# CAN_BUS.net
KiCad netlist of a schematic drawn in Altium Designer
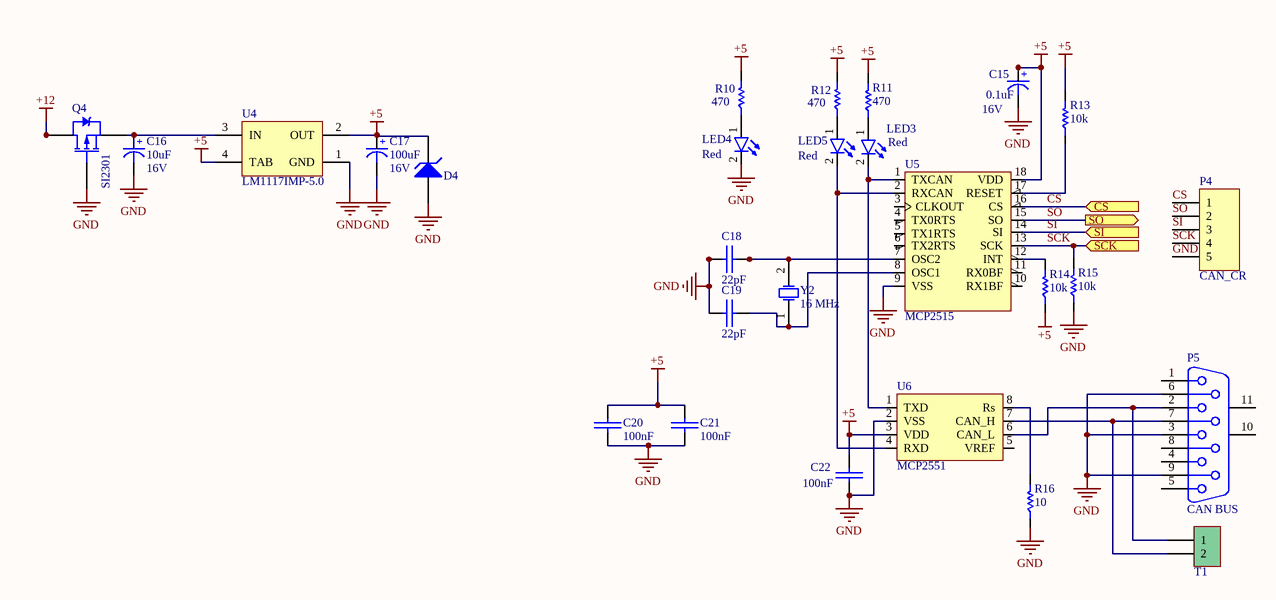
[diagram p0: CAN_BUS.SchDoc]

(export (version "E")
  (design (tool "Eeschema 10.0.6"))
  (components
    (comp (ref "C15")
      (value "0.1uF")
      (footprint "CAPP 1206 (3216X18L) Size A")
      (description "Polar Capacitor")
      (fields (field (name "VOLTAGE") "16V") (field (name "DESIGNER") "Saeid Jorablo"))
      (libsource (lib "My_Library") (part "Cap-Polar"))
    )
    (comp (ref "C16")
      (value "10uF")
      (footprint "CAPP 1206 (3216X18L) Size A")
      (description "Polar Capacitor")
      (fields (field (name "VOLTAGE") "16V") (field (name "DESIGNER") "Saeid Jorablo"))
      (libsource (lib "My_Library") (part "Cap-Polar"))
    )
    (comp (ref "C17")
      (value "100uF")
      (footprint "CAPP 1206 (3216X18L) Size A")
      (description "Polar Capacitor")
      (fields (field (name "VOLTAGE") "16V") (field (name "DESIGNER") "Saeid Jorablo"))
      (libsource (lib "My_Library") (part "Cap-Polar"))
    )
    (comp (ref "C18")
      (value "22pF")
      (footprint "SMD_CAP_1206")
      (description "Bipolar Capacitor")
      (fields (field (name "VOLTAGE") "100V") (field (name "DESIGNER") "Saeid Jorablo"))
      (libsource (lib "My_Library") (part "Cap-Bipolar"))
    )
    (comp (ref "C19")
      (value "22pF")
      (footprint "SMD_CAP_1206")
      (description "Bipolar Capacitor")
      (fields (field (name "VOLTAGE") "100V") (field (name "DESIGNER") "Saeid Jorablo"))
      (libsource (lib "My_Library") (part "Cap-Bipolar"))
    )
    (comp (ref "C20")
      (value "100nF")
      (footprint "SMD_CAP_1206")
      (description "Bipolar Capacitor")
      (fields (field (name "VOLTAGE") "100V") (field (name "DESIGNER") "Saeid Jorablo"))
      (libsource (lib "My_Library") (part "Cap-Bipolar"))
    )
    (comp (ref "C21")
      (value "100nF")
      (footprint "SMD_CAP_1206")
      (description "Bipolar Capacitor")
      (fields (field (name "VOLTAGE") "100V") (field (name "DESIGNER") "Saeid Jorablo"))
      (libsource (lib "My_Library") (part "Cap-Bipolar"))
    )
    (comp (ref "C22")
      (value "100nF")
      (footprint "SMD_CAP_1206")
      (description "Bipolar Capacitor")
      (fields (field (name "VOLTAGE") "100V") (field (name "DESIGNER") "Saeid Jorablo"))
      (libsource (lib "My_Library") (part "Cap-Bipolar"))
    )
    (comp (ref "D4")
      (value "Diode Zener")
      (footprint "Diode 1W")
      (description "Zener Diode")
      (fields (field (name "VOLTAGE") "5 V") (field (name "DESIGNER") "Saeid Jorablo"))
      (libsource (lib "My_Library") (part "Diode Zener"))
    )
    (comp (ref "LED3")
      (value "Red")
      (footprint "LED-5mm")
      (description "LED")
      (fields (field (name "COLOR") "Red") (field (name "DESIGNER") "Saeid Jorablo"))
      (libsource (lib "My_Library") (part "LED"))
    )
    (comp (ref "LED4")
      (value "Red")
      (footprint "LED-5mm")
      (description "LED")
      (fields (field (name "COLOR") "Red") (field (name "DESIGNER") "Saeid Jorablo"))
      (libsource (lib "My_Library") (part "LED"))
    )
    (comp (ref "LED5")
      (value "Red")
      (footprint "LED-5mm")
      (description "LED")
      (fields (field (name "COLOR") "Red") (field (name "DESIGNER") "Saeid Jorablo"))
      (libsource (lib "My_Library") (part "LED"))
    )
    (comp (ref "P4")
      (value "CAN_CR")
      (footprint "HDR1X5")
      (description "Header, 5-Pin")
      (fields (field (name "PUBLISHER") "Altium Limited"))
      (libsource (lib "Miscellaneous Connectors") (part "Header 5"))
    )
    (comp (ref "P5")
      (value "CAN BUS")
      (footprint "DB9 Female")
      (description "Receptacle Assembly, 9 Position, Right Angle")
      (fields (field (name "PUBLISHER") "Altium Limited"))
      (libsource (lib "My_Library") (part "DB9 Connector"))
    )
    (comp (ref "Q4")
      (value "SI2301")
      (footprint "SOT-23_M")
      (description "P-Channel Power MOSFET")
      (fields (field (name "PUBLISHER") "Altium Limited"))
      (libsource (lib "Miscellaneous Devices") (part "PMOS-2"))
    )
    (comp (ref "R10")
      (value "470")
      (footprint "RES 1206 (3216X08L)")
      (description "Resistor")
      (libsource (lib "My_Library") (part "Resistor"))
    )
    (comp (ref "R11")
      (value "470")
      (footprint "RES 1206 (3216X08L)")
      (description "Resistor")
      (libsource (lib "My_Library") (part "Resistor"))
    )
    (comp (ref "R12")
      (value "470")
      (footprint "RES 1206 (3216X08L)")
      (description "Resistor")
      (libsource (lib "My_Library") (part "Resistor"))
    )
    (comp (ref "R13")
      (value "10k")
      (footprint "RES 1206 (3216X08L)")
      (description "Resistor")
      (libsource (lib "My_Library") (part "Resistor"))
    )
    (comp (ref "R14")
      (value "10k")
      (footprint "RES 1206 (3216X08L)")
      (description "Resistor")
      (libsource (lib "My_Library") (part "Resistor"))
    )
    (comp (ref "R15")
      (value "10k")
      (footprint "RES 1206 (3216X08L)")
      (description "Resistor")
      (libsource (lib "My_Library") (part "Resistor"))
    )
    (comp (ref "R16")
      (value "10")
      (footprint "RES 1206 (3216X08L)")
      (description "Resistor")
      (libsource (lib "My_Library") (part "Resistor"))
    )
    (comp (ref "T1")
      (value "Phoenix terminal")
      (footprint "Phoenix2")
      (description "Terminal 2 Pin")
      (fields (field (name "DESIGNER") "Seyed Mohsen Ghasemain") (field (name "E-MAIL") "picpars@gmail.com"))
      (libsource (lib "usefully_Library") (part "Phoenix terminal 2"))
    )
    (comp (ref "U4")
      (value "LM1117IMP-5.0")
      (footprint "MP04A_N")
      (description "5 Volt, 800mA Low-Dropout Linear Regulator, 4-pin SOT-223")
      (fields
        (field (name "PARTNUMBER") "LM1117IMP-3.3")
        (field (name "MANUFACTURER") "National Semiconductor")
        (field (name "PUBLISHER") "Altium Limited")
      )
      (libsource (lib "My_Library") (part "LM1117IMP-x.x"))
    )
    (comp (ref "U5")
      (value "MCP2515")
      (footprint "SOIC18-N")
      (description "CAN Bus controller")
      (libsource (lib "JRLib") (part "MCP2515"))
    )
    (comp (ref "U6")
      (value "MCP2551")
      (footprint "SOIC8")
      (description "CAN Bus controller")
      (libsource (lib "JRLib") (part "MCP2551"))
    )
    (comp (ref "Y2")
      (value "16 MHz")
      (footprint "XTAL")
      (description "XTAL Crystal")
      (libsource (lib "My_Library") (part "XTAL"))
    )
  )
  (nets
    (net (code "1") (name "+5") (class "Default")
      (node (ref "C15") (pin "1") (pinfunction "+_1") (pintype "passive"))
      (node (ref "C17") (pin "1") (pinfunction "+_1") (pintype "passive"))
      (node (ref "C20") (pin "1") (pinfunction "+_1") (pintype "passive"))
      (node (ref "C21") (pin "1") (pinfunction "+_1") (pintype "passive"))
      (node (ref "C22") (pin "1") (pinfunction "+_1") (pintype "passive"))
      (node (ref "D4") (pin "2") (pinfunction "K_2") (pintype "passive"))
      (node (ref "R10") (pin "2") (pinfunction "2_2") (pintype "passive"))
      (node (ref "R11") (pin "2") (pinfunction "2_2") (pintype "passive"))
      (node (ref "R12") (pin "2") (pinfunction "2_2") (pintype "passive"))
      (node (ref "R13") (pin "2") (pinfunction "2_2") (pintype "passive"))
      (node (ref "R14") (pin "1") (pinfunction "1_1") (pintype "passive"))
      (node (ref "U4") (pin "2") (pinfunction "OUT_2") (pintype "power_in"))
      (node (ref "U4") (pin "4") (pinfunction "TAB_4") (pintype "power_in"))
      (node (ref "U5") (pin "18") (pinfunction "VDD_18") (pintype "passive"))
      (node (ref "U6") (pin "3") (pinfunction "VDD_3") (pintype "passive"))
    )
    (net (code "2") (name "+12") (class "Default")
      (node (ref "Q4") (pin "2") (pinfunction "D_2") (pintype "passive"))
    )
    (net (code "3") (name "/CS") (class "Default")
      (node (ref "P4") (pin "1") (pinfunction "1_1") (pintype "passive"))
      (node (ref "U5") (pin "16") (pinfunction "CS_16") (pintype "passive"))
    )
    (net (code "4") (name "/SCK") (class "Default")
      (node (ref "P4") (pin "4") (pinfunction "4_4") (pintype "passive"))
      (node (ref "R15") (pin "2") (pinfunction "2_2") (pintype "passive"))
      (node (ref "U5") (pin "13") (pinfunction "SCK_13") (pintype "passive"))
    )
    (net (code "5") (name "/SI") (class "Default")
      (node (ref "P4") (pin "3") (pinfunction "3_3") (pintype "passive"))
      (node (ref "U5") (pin "14") (pinfunction "SI_14") (pintype "passive"))
    )
    (net (code "6") (name "/SO") (class "Default")
      (node (ref "P4") (pin "2") (pinfunction "2_2") (pintype "passive"))
      (node (ref "U5") (pin "15") (pinfunction "SO_15") (pintype "passive"))
    )
    (net (code "7") (name "GND") (class "Default")
      (node (ref "C15") (pin "2") (pinfunction "-_2") (pintype "passive"))
      (node (ref "C16") (pin "2") (pinfunction "-_2") (pintype "passive"))
      (node (ref "C17") (pin "2") (pinfunction "-_2") (pintype "passive"))
      (node (ref "C18") (pin "1") (pinfunction "+_1") (pintype "passive"))
      (node (ref "C19") (pin "1") (pinfunction "+_1") (pintype "passive"))
      (node (ref "C20") (pin "2") (pinfunction "-_2") (pintype "passive"))
      (node (ref "C21") (pin "2") (pinfunction "-_2") (pintype "passive"))
      (node (ref "C22") (pin "2") (pinfunction "-_2") (pintype "passive"))
      (node (ref "D4") (pin "1") (pinfunction "A_1") (pintype "passive"))
      (node (ref "LED4") (pin "2") (pinfunction "K_2") (pintype "passive"))
      (node (ref "P4") (pin "5") (pinfunction "5_5") (pintype "passive"))
      (node (ref "P5") (pin "3") (pinfunction "3_3") (pintype "passive"))
      (node (ref "P5") (pin "6") (pinfunction "6_6") (pintype "passive"))
      (node (ref "P5") (pin "9") (pinfunction "9_9") (pintype "passive"))
      (node (ref "Q4") (pin "1") (pinfunction "G_1") (pintype "passive"))
      (node (ref "R15") (pin "1") (pinfunction "1_1") (pintype "passive"))
      (node (ref "R16") (pin "1") (pinfunction "1_1") (pintype "passive"))
      (node (ref "U4") (pin "1") (pinfunction "GND_1") (pintype "power_in"))
      (node (ref "U5") (pin "9") (pinfunction "VSS_9") (pintype "passive"))
      (node (ref "U6") (pin "2") (pinfunction "VSS_2") (pintype "passive"))
    )
    (net (code "8") (name "Net-(C16-+)") (class "Default")
      (node (ref "C16") (pin "1") (pinfunction "+_1") (pintype "passive"))
      (node (ref "Q4") (pin "3") (pinfunction "S_3") (pintype "passive"))
      (node (ref "U4") (pin "3") (pinfunction "IN_3") (pintype "power_in"))
    )
    (net (code "9") (name "Net-(C18--)") (class "Default")
      (node (ref "C18") (pin "2") (pinfunction "-_2") (pintype "passive"))
      (node (ref "U5") (pin "7") (pinfunction "OSC2_7") (pintype "passive"))
      (node (ref "Y2") (pin "2") (pinfunction "OSC2_2") (pintype "passive"))
    )
    (net (code "10") (name "Net-(C19--)") (class "Default")
      (node (ref "C19") (pin "2") (pinfunction "-_2") (pintype "passive"))
      (node (ref "U5") (pin "8") (pinfunction "OSC1_8") (pintype "passive"))
      (node (ref "Y2") (pin "1") (pinfunction "OSC1_1") (pintype "passive"))
    )
    (net (code "11") (name "Net-(LED3-A)") (class "Default")
      (node (ref "LED3") (pin "1") (pinfunction "A_1") (pintype "passive"))
      (node (ref "R11") (pin "1") (pinfunction "1_1") (pintype "passive"))
    )
    (net (code "12") (name "Net-(LED3-K)") (class "Default")
      (node (ref "LED3") (pin "2") (pinfunction "K_2") (pintype "passive"))
      (node (ref "U5") (pin "1") (pinfunction "TXCAN_1") (pintype "passive"))
      (node (ref "U6") (pin "1") (pinfunction "TXD_1") (pintype "passive"))
    )
    (net (code "13") (name "Net-(LED4-A)") (class "Default")
      (node (ref "LED4") (pin "1") (pinfunction "A_1") (pintype "passive"))
      (node (ref "R10") (pin "1") (pinfunction "1_1") (pintype "passive"))
    )
    (net (code "14") (name "Net-(LED5-A)") (class "Default")
      (node (ref "LED5") (pin "1") (pinfunction "A_1") (pintype "passive"))
      (node (ref "R12") (pin "1") (pinfunction "1_1") (pintype "passive"))
    )
    (net (code "15") (name "Net-(LED5-K)") (class "Default")
      (node (ref "LED5") (pin "2") (pinfunction "K_2") (pintype "passive"))
      (node (ref "U5") (pin "2") (pinfunction "RXCAN_2") (pintype "passive"))
      (node (ref "U6") (pin "4") (pinfunction "RXD_4") (pintype "passive"))
    )
    (net (code "16") (name "Net-(U5-INT)") (class "Default")
      (node (ref "R14") (pin "2") (pinfunction "2_2") (pintype "passive"))
      (node (ref "U5") (pin "12") (pinfunction "INT_12") (pintype "passive"))
    )
    (net (code "17") (name "Net-(U5-RESET)") (class "Default")
      (node (ref "R13") (pin "1") (pinfunction "1_1") (pintype "passive"))
      (node (ref "U5") (pin "17") (pinfunction "RESET_17") (pintype "passive"))
    )
    (net (code "18") (name "Net-(U6-CAN_H)") (class "Default")
      (node (ref "P5") (pin "7") (pinfunction "7_7") (pintype "passive"))
      (node (ref "T1") (pin "2") (pinfunction "2_2") (pintype "passive"))
      (node (ref "U6") (pin "7") (pinfunction "CAN_H_7") (pintype "passive"))
    )
    (net (code "19") (name "Net-(U6-CAN_L)") (class "Default")
      (node (ref "P5") (pin "2") (pinfunction "2_2") (pintype "passive"))
      (node (ref "T1") (pin "1") (pinfunction "1_1") (pintype "passive"))
      (node (ref "U6") (pin "6") (pinfunction "CAN_L_6") (pintype "passive"))
    )
    (net (code "20") (name "Net-(U6-Rs)") (class "Default")
      (node (ref "R16") (pin "2") (pinfunction "2_2") (pintype "passive"))
      (node (ref "U6") (pin "8") (pinfunction "Rs_8") (pintype "passive"))
    )
    (net (code "21") (name "unconnected-(P5-MH1-Pad10)") (class "Default")
      (node (ref "P5") (pin "10") (pinfunction "MH1_10") (pintype "passive"))
    )
    (net (code "22") (name "unconnected-(P5-MH2-Pad11)") (class "Default")
      (node (ref "P5") (pin "11") (pinfunction "MH2_11") (pintype "passive"))
    )
    (net (code "23") (name "unconnected-(P5-Pad1)") (class "Default")
      (node (ref "P5") (pin "1") (pinfunction "1_1") (pintype "passive"))
    )
    (net (code "24") (name "unconnected-(P5-Pad4)") (class "Default")
      (node (ref "P5") (pin "4") (pinfunction "4_4") (pintype "passive"))
    )
    (net (code "25") (name "unconnected-(P5-Pad5)") (class "Default")
      (node (ref "P5") (pin "5") (pinfunction "5_5") (pintype "passive"))
    )
    (net (code "26") (name "unconnected-(P5-Pad8)") (class "Default")
      (node (ref "P5") (pin "8") (pinfunction "8_8") (pintype "passive"))
    )
    (net (code "27") (name "unconnected-(U5-CLKOUT-Pad3)") (class "Default")
      (node (ref "U5") (pin "3") (pinfunction "CLKOUT_3") (pintype "passive"))
    )
    (net (code "28") (name "unconnected-(U5-RX0BF-Pad11)") (class "Default")
      (node (ref "U5") (pin "11") (pinfunction "RX0BF_11") (pintype "passive"))
    )
    (net (code "29") (name "unconnected-(U5-RX1BF-Pad10)") (class "Default")
      (node (ref "U5") (pin "10") (pinfunction "RX1BF_10") (pintype "passive"))
    )
    (net (code "30") (name "unconnected-(U5-TX0RTS-Pad4)") (class "Default")
      (node (ref "U5") (pin "4") (pinfunction "TX0RTS_4") (pintype "passive"))
    )
    (net (code "31") (name "unconnected-(U5-TX1RTS-Pad5)") (class "Default")
      (node (ref "U5") (pin "5") (pinfunction "TX1RTS_5") (pintype "passive"))
    )
    (net (code "32") (name "unconnected-(U5-TX2RTS-Pad6)") (class "Default")
      (node (ref "U5") (pin "6") (pinfunction "TX2RTS_6") (pintype "passive"))
    )
    (net (code "33") (name "unconnected-(U6-VREF-Pad5)") (class "Default")
      (node (ref "U6") (pin "5") (pinfunction "VREF_5") (pintype "passive"))
    )
  )
)
